# ADC-ADC_PSU.net
KiCad netlist of a schematic drawn in Altium Designer
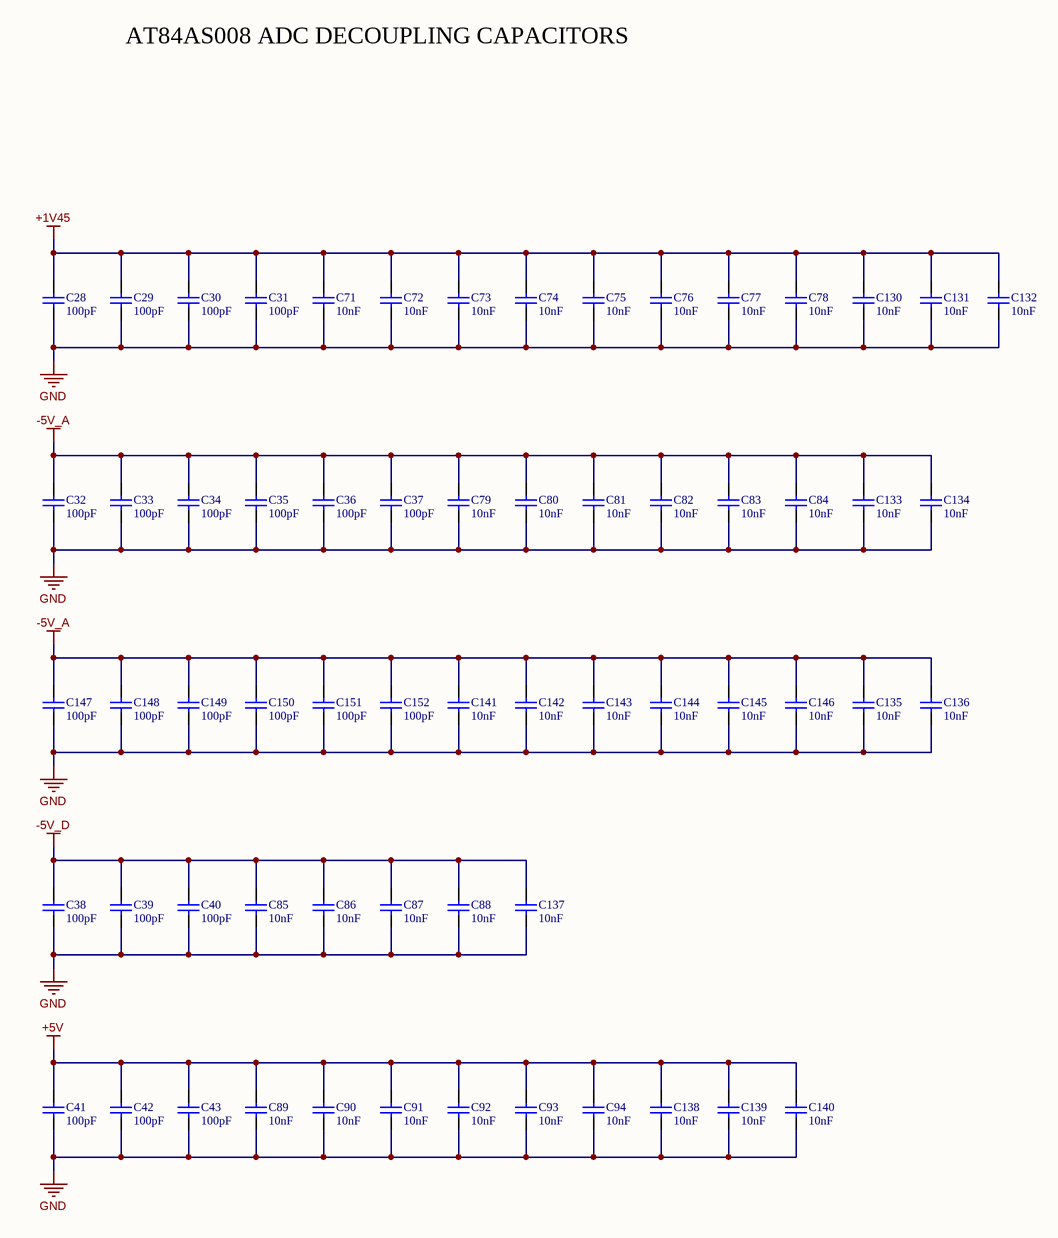
[diagram p0: ADC-ADC PSU.SchDoc]

(export (version "E")
  (design (tool "Eeschema 10.0.6"))
  (components
    (comp (ref "C28")
      (value "100pF")
      (footprint "CAPC1005X55N")
      (description "Capacitor 0402 SMD")
      (fields (field (name "CREATED_BY") "EDA-ASA") (field (name "CHECKED_BY") "*"))
      (libsource (lib "EDA-Passive") (part "cap0402"))
    )
    (comp (ref "C29")
      (value "100pF")
      (footprint "CAPC1005X55N")
      (description "Capacitor 0402 SMD")
      (fields (field (name "CREATED_BY") "EDA-ASA") (field (name "CHECKED_BY") "*"))
      (libsource (lib "EDA-Passive") (part "cap0402"))
    )
    (comp (ref "C30")
      (value "100pF")
      (footprint "CAPC1005X55N")
      (description "Capacitor 0402 SMD")
      (fields (field (name "CREATED_BY") "EDA-ASA") (field (name "CHECKED_BY") "*"))
      (libsource (lib "EDA-Passive") (part "cap0402"))
    )
    (comp (ref "C31")
      (value "100pF")
      (footprint "CAPC1005X55N")
      (description "Capacitor 0402 SMD")
      (fields (field (name "CREATED_BY") "EDA-ASA") (field (name "CHECKED_BY") "*"))
      (libsource (lib "EDA-Passive") (part "cap0402"))
    )
    (comp (ref "C32")
      (value "100pF")
      (footprint "CAPC1005X55N")
      (description "Capacitor 0402 SMD")
      (fields (field (name "CREATED_BY") "EDA-ASA") (field (name "CHECKED_BY") "*"))
      (libsource (lib "EDA-Passive") (part "cap0402"))
    )
    (comp (ref "C33")
      (value "100pF")
      (footprint "CAPC1005X55N")
      (description "Capacitor 0402 SMD")
      (fields (field (name "CREATED_BY") "EDA-ASA") (field (name "CHECKED_BY") "*"))
      (libsource (lib "EDA-Passive") (part "cap0402"))
    )
    (comp (ref "C34")
      (value "100pF")
      (footprint "CAPC1005X55N")
      (description "Capacitor 0402 SMD")
      (fields (field (name "CREATED_BY") "EDA-ASA") (field (name "CHECKED_BY") "*"))
      (libsource (lib "EDA-Passive") (part "cap0402"))
    )
    (comp (ref "C35")
      (value "100pF")
      (footprint "CAPC1005X55N")
      (description "Capacitor 0402 SMD")
      (fields (field (name "CREATED_BY") "EDA-ASA") (field (name "CHECKED_BY") "*"))
      (libsource (lib "EDA-Passive") (part "cap0402"))
    )
    (comp (ref "C36")
      (value "100pF")
      (footprint "CAPC1005X55N")
      (description "Capacitor 0402 SMD")
      (fields (field (name "CREATED_BY") "EDA-ASA") (field (name "CHECKED_BY") "*"))
      (libsource (lib "EDA-Passive") (part "cap0402"))
    )
    (comp (ref "C37")
      (value "100pF")
      (footprint "CAPC1005X55N")
      (description "Capacitor 0402 SMD")
      (fields (field (name "CREATED_BY") "EDA-ASA") (field (name "CHECKED_BY") "*"))
      (libsource (lib "EDA-Passive") (part "cap0402"))
    )
    (comp (ref "C38")
      (value "100pF")
      (footprint "CAPC1005X55N")
      (description "Capacitor 0402 SMD")
      (fields (field (name "CREATED_BY") "EDA-ASA") (field (name "CHECKED_BY") "*"))
      (libsource (lib "EDA-Passive") (part "cap0402"))
    )
    (comp (ref "C39")
      (value "100pF")
      (footprint "CAPC1005X55N")
      (description "Capacitor 0402 SMD")
      (fields (field (name "CREATED_BY") "EDA-ASA") (field (name "CHECKED_BY") "*"))
      (libsource (lib "EDA-Passive") (part "cap0402"))
    )
    (comp (ref "C40")
      (value "100pF")
      (footprint "CAPC1005X55N")
      (description "Capacitor 0402 SMD")
      (fields (field (name "CREATED_BY") "EDA-ASA") (field (name "CHECKED_BY") "*"))
      (libsource (lib "EDA-Passive") (part "cap0402"))
    )
    (comp (ref "C41")
      (value "100pF")
      (footprint "CAPC1005X55N")
      (description "Capacitor 0402 SMD")
      (fields (field (name "CREATED_BY") "EDA-ASA") (field (name "CHECKED_BY") "*"))
      (libsource (lib "EDA-Passive") (part "cap0402"))
    )
    (comp (ref "C42")
      (value "100pF")
      (footprint "CAPC1005X55N")
      (description "Capacitor 0402 SMD")
      (fields (field (name "CREATED_BY") "EDA-ASA") (field (name "CHECKED_BY") "*"))
      (libsource (lib "EDA-Passive") (part "cap0402"))
    )
    (comp (ref "C43")
      (value "100pF")
      (footprint "CAPC1005X55N")
      (description "Capacitor 0402 SMD")
      (fields (field (name "CREATED_BY") "EDA-ASA") (field (name "CHECKED_BY") "*"))
      (libsource (lib "EDA-Passive") (part "cap0402"))
    )
    (comp (ref "C71")
      (value "10nF")
      (footprint "CAPC1005X55N")
      (description "Capacitor 0402 SMD")
      (fields (field (name "CREATED_BY") "EDA-ASA") (field (name "CHECKED_BY") "*"))
      (libsource (lib "EDA-Passive") (part "cap0402"))
    )
    (comp (ref "C72")
      (value "10nF")
      (footprint "CAPC1005X55N")
      (description "Capacitor 0402 SMD")
      (fields (field (name "CREATED_BY") "EDA-ASA") (field (name "CHECKED_BY") "*"))
      (libsource (lib "EDA-Passive") (part "cap0402"))
    )
    (comp (ref "C73")
      (value "10nF")
      (footprint "CAPC1005X55N")
      (description "Capacitor 0402 SMD")
      (fields (field (name "CREATED_BY") "EDA-ASA") (field (name "CHECKED_BY") "*"))
      (libsource (lib "EDA-Passive") (part "cap0402"))
    )
    (comp (ref "C74")
      (value "10nF")
      (footprint "CAPC1005X55N")
      (description "Capacitor 0402 SMD")
      (fields (field (name "CREATED_BY") "EDA-ASA") (field (name "CHECKED_BY") "*"))
      (libsource (lib "EDA-Passive") (part "cap0402"))
    )
    (comp (ref "C75")
      (value "10nF")
      (footprint "CAPC1005X55N")
      (description "Capacitor 0402 SMD")
      (fields (field (name "CREATED_BY") "EDA-ASA") (field (name "CHECKED_BY") "*"))
      (libsource (lib "EDA-Passive") (part "cap0402"))
    )
    (comp (ref "C76")
      (value "10nF")
      (footprint "CAPC1005X55N")
      (description "Capacitor 0402 SMD")
      (fields (field (name "CREATED_BY") "EDA-ASA") (field (name "CHECKED_BY") "*"))
      (libsource (lib "EDA-Passive") (part "cap0402"))
    )
    (comp (ref "C77")
      (value "10nF")
      (footprint "CAPC1005X55N")
      (description "Capacitor 0402 SMD")
      (fields (field (name "CREATED_BY") "EDA-ASA") (field (name "CHECKED_BY") "*"))
      (libsource (lib "EDA-Passive") (part "cap0402"))
    )
    (comp (ref "C78")
      (value "10nF")
      (footprint "CAPC1005X55N")
      (description "Capacitor 0402 SMD")
      (fields (field (name "CREATED_BY") "EDA-ASA") (field (name "CHECKED_BY") "*"))
      (libsource (lib "EDA-Passive") (part "cap0402"))
    )
    (comp (ref "C79")
      (value "10nF")
      (footprint "CAPC1005X55N")
      (description "Capacitor 0402 SMD")
      (fields (field (name "CREATED_BY") "EDA-ASA") (field (name "CHECKED_BY") "*"))
      (libsource (lib "EDA-Passive") (part "cap0402"))
    )
    (comp (ref "C80")
      (value "10nF")
      (footprint "CAPC1005X55N")
      (description "Capacitor 0402 SMD")
      (fields (field (name "CREATED_BY") "EDA-ASA") (field (name "CHECKED_BY") "*"))
      (libsource (lib "EDA-Passive") (part "cap0402"))
    )
    (comp (ref "C81")
      (value "10nF")
      (footprint "CAPC1005X55N")
      (description "Capacitor 0402 SMD")
      (fields (field (name "CREATED_BY") "EDA-ASA") (field (name "CHECKED_BY") "*"))
      (libsource (lib "EDA-Passive") (part "cap0402"))
    )
    (comp (ref "C82")
      (value "10nF")
      (footprint "CAPC1005X55N")
      (description "Capacitor 0402 SMD")
      (fields (field (name "CREATED_BY") "EDA-ASA") (field (name "CHECKED_BY") "*"))
      (libsource (lib "EDA-Passive") (part "cap0402"))
    )
    (comp (ref "C83")
      (value "10nF")
      (footprint "CAPC1005X55N")
      (description "Capacitor 0402 SMD")
      (fields (field (name "CREATED_BY") "EDA-ASA") (field (name "CHECKED_BY") "*"))
      (libsource (lib "EDA-Passive") (part "cap0402"))
    )
    (comp (ref "C84")
      (value "10nF")
      (footprint "CAPC1005X55N")
      (description "Capacitor 0402 SMD")
      (fields (field (name "CREATED_BY") "EDA-ASA") (field (name "CHECKED_BY") "*"))
      (libsource (lib "EDA-Passive") (part "cap0402"))
    )
    (comp (ref "C85")
      (value "10nF")
      (footprint "CAPC1005X55N")
      (description "Capacitor 0402 SMD")
      (fields (field (name "CREATED_BY") "EDA-ASA") (field (name "CHECKED_BY") "*"))
      (libsource (lib "EDA-Passive") (part "cap0402"))
    )
    (comp (ref "C86")
      (value "10nF")
      (footprint "CAPC1005X55N")
      (description "Capacitor 0402 SMD")
      (fields (field (name "CREATED_BY") "EDA-ASA") (field (name "CHECKED_BY") "*"))
      (libsource (lib "EDA-Passive") (part "cap0402"))
    )
    (comp (ref "C87")
      (value "10nF")
      (footprint "CAPC1005X55N")
      (description "Capacitor 0402 SMD")
      (fields (field (name "CREATED_BY") "EDA-ASA") (field (name "CHECKED_BY") "*"))
      (libsource (lib "EDA-Passive") (part "cap0402"))
    )
    (comp (ref "C88")
      (value "10nF")
      (footprint "CAPC1005X55N")
      (description "Capacitor 0402 SMD")
      (fields (field (name "CREATED_BY") "EDA-ASA") (field (name "CHECKED_BY") "*"))
      (libsource (lib "EDA-Passive") (part "cap0402"))
    )
    (comp (ref "C89")
      (value "10nF")
      (footprint "CAPC1005X55N")
      (description "Capacitor 0402 SMD")
      (fields (field (name "CREATED_BY") "EDA-ASA") (field (name "CHECKED_BY") "*"))
      (libsource (lib "EDA-Passive") (part "cap0402"))
    )
    (comp (ref "C90")
      (value "10nF")
      (footprint "CAPC1005X55N")
      (description "Capacitor 0402 SMD")
      (fields (field (name "CREATED_BY") "EDA-ASA") (field (name "CHECKED_BY") "*"))
      (libsource (lib "EDA-Passive") (part "cap0402"))
    )
    (comp (ref "C91")
      (value "10nF")
      (footprint "CAPC1005X55N")
      (description "Capacitor 0402 SMD")
      (fields (field (name "CREATED_BY") "EDA-ASA") (field (name "CHECKED_BY") "*"))
      (libsource (lib "EDA-Passive") (part "cap0402"))
    )
    (comp (ref "C92")
      (value "10nF")
      (footprint "CAPC1005X55N")
      (description "Capacitor 0402 SMD")
      (fields (field (name "CREATED_BY") "EDA-ASA") (field (name "CHECKED_BY") "*"))
      (libsource (lib "EDA-Passive") (part "cap0402"))
    )
    (comp (ref "C93")
      (value "10nF")
      (footprint "CAPC1005X55N")
      (description "Capacitor 0402 SMD")
      (fields (field (name "CREATED_BY") "EDA-ASA") (field (name "CHECKED_BY") "*"))
      (libsource (lib "EDA-Passive") (part "cap0402"))
    )
    (comp (ref "C94")
      (value "10nF")
      (footprint "CAPC1005X55N")
      (description "Capacitor 0402 SMD")
      (fields (field (name "CREATED_BY") "EDA-ASA") (field (name "CHECKED_BY") "*"))
      (libsource (lib "EDA-Passive") (part "cap0402"))
    )
    (comp (ref "C130")
      (value "10nF")
      (footprint "CAPC1005X55N")
      (description "Capacitor 0402 SMD")
      (fields (field (name "CREATED_BY") "EDA-ASA") (field (name "CHECKED_BY") "*"))
      (libsource (lib "EDA-Passive") (part "cap0402"))
    )
    (comp (ref "C131")
      (value "10nF")
      (footprint "CAPC1005X55N")
      (description "Capacitor 0402 SMD")
      (fields (field (name "CREATED_BY") "EDA-ASA") (field (name "CHECKED_BY") "*"))
      (libsource (lib "EDA-Passive") (part "cap0402"))
    )
    (comp (ref "C132")
      (value "10nF")
      (footprint "CAPC1005X55N")
      (description "Capacitor 0402 SMD")
      (fields (field (name "CREATED_BY") "EDA-ASA") (field (name "CHECKED_BY") "*"))
      (libsource (lib "EDA-Passive") (part "cap0402"))
    )
    (comp (ref "C133")
      (value "10nF")
      (footprint "CAPC1005X55N")
      (description "Capacitor 0402 SMD")
      (fields (field (name "CREATED_BY") "EDA-ASA") (field (name "CHECKED_BY") "*"))
      (libsource (lib "EDA-Passive") (part "cap0402"))
    )
    (comp (ref "C134")
      (value "10nF")
      (footprint "CAPC1005X55N")
      (description "Capacitor 0402 SMD")
      (fields (field (name "CREATED_BY") "EDA-ASA") (field (name "CHECKED_BY") "*"))
      (libsource (lib "EDA-Passive") (part "cap0402"))
    )
    (comp (ref "C135")
      (value "10nF")
      (footprint "CAPC1005X55N")
      (description "Capacitor 0402 SMD")
      (fields (field (name "CREATED_BY") "EDA-ASA") (field (name "CHECKED_BY") "*"))
      (libsource (lib "EDA-Passive") (part "cap0402"))
    )
    (comp (ref "C136")
      (value "10nF")
      (footprint "CAPC1005X55N")
      (description "Capacitor 0402 SMD")
      (fields (field (name "CREATED_BY") "EDA-ASA") (field (name "CHECKED_BY") "*"))
      (libsource (lib "EDA-Passive") (part "cap0402"))
    )
    (comp (ref "C137")
      (value "10nF")
      (footprint "CAPC1005X55N")
      (description "Capacitor 0402 SMD")
      (fields (field (name "CREATED_BY") "EDA-ASA") (field (name "CHECKED_BY") "*"))
      (libsource (lib "EDA-Passive") (part "cap0402"))
    )
    (comp (ref "C138")
      (value "10nF")
      (footprint "CAPC1005X55N")
      (description "Capacitor 0402 SMD")
      (fields (field (name "CREATED_BY") "EDA-ASA") (field (name "CHECKED_BY") "*"))
      (libsource (lib "EDA-Passive") (part "cap0402"))
    )
    (comp (ref "C139")
      (value "10nF")
      (footprint "CAPC1005X55N")
      (description "Capacitor 0402 SMD")
      (fields (field (name "CREATED_BY") "EDA-ASA") (field (name "CHECKED_BY") "*"))
      (libsource (lib "EDA-Passive") (part "cap0402"))
    )
    (comp (ref "C140")
      (value "10nF")
      (footprint "CAPC1005X55N")
      (description "Capacitor 0402 SMD")
      (fields (field (name "CREATED_BY") "EDA-ASA") (field (name "CHECKED_BY") "*"))
      (libsource (lib "EDA-Passive") (part "cap0402"))
    )
    (comp (ref "C141")
      (value "10nF")
      (footprint "CAPC1005X55N")
      (description "Capacitor 0402 SMD")
      (fields (field (name "CREATED_BY") "EDA-ASA") (field (name "CHECKED_BY") "*"))
      (libsource (lib "EDA-Passive") (part "cap0402"))
    )
    (comp (ref "C142")
      (value "10nF")
      (footprint "CAPC1005X55N")
      (description "Capacitor 0402 SMD")
      (fields (field (name "CREATED_BY") "EDA-ASA") (field (name "CHECKED_BY") "*"))
      (libsource (lib "EDA-Passive") (part "cap0402"))
    )
    (comp (ref "C143")
      (value "10nF")
      (footprint "CAPC1005X55N")
      (description "Capacitor 0402 SMD")
      (fields (field (name "CREATED_BY") "EDA-ASA") (field (name "CHECKED_BY") "*"))
      (libsource (lib "EDA-Passive") (part "cap0402"))
    )
    (comp (ref "C144")
      (value "10nF")
      (footprint "CAPC1005X55N")
      (description "Capacitor 0402 SMD")
      (fields (field (name "CREATED_BY") "EDA-ASA") (field (name "CHECKED_BY") "*"))
      (libsource (lib "EDA-Passive") (part "cap0402"))
    )
    (comp (ref "C145")
      (value "10nF")
      (footprint "CAPC1005X55N")
      (description "Capacitor 0402 SMD")
      (fields (field (name "CREATED_BY") "EDA-ASA") (field (name "CHECKED_BY") "*"))
      (libsource (lib "EDA-Passive") (part "cap0402"))
    )
    (comp (ref "C146")
      (value "10nF")
      (footprint "CAPC1005X55N")
      (description "Capacitor 0402 SMD")
      (fields (field (name "CREATED_BY") "EDA-ASA") (field (name "CHECKED_BY") "*"))
      (libsource (lib "EDA-Passive") (part "cap0402"))
    )
    (comp (ref "C147")
      (value "100pF")
      (footprint "CAPC1005X55N")
      (description "Capacitor 0402 SMD")
      (fields (field (name "CREATED_BY") "EDA-ASA") (field (name "CHECKED_BY") "*"))
      (libsource (lib "EDA-Passive") (part "cap0402"))
    )
    (comp (ref "C148")
      (value "100pF")
      (footprint "CAPC1005X55N")
      (description "Capacitor 0402 SMD")
      (fields (field (name "CREATED_BY") "EDA-ASA") (field (name "CHECKED_BY") "*"))
      (libsource (lib "EDA-Passive") (part "cap0402"))
    )
    (comp (ref "C149")
      (value "100pF")
      (footprint "CAPC1005X55N")
      (description "Capacitor 0402 SMD")
      (fields (field (name "CREATED_BY") "EDA-ASA") (field (name "CHECKED_BY") "*"))
      (libsource (lib "EDA-Passive") (part "cap0402"))
    )
    (comp (ref "C150")
      (value "100pF")
      (footprint "CAPC1005X55N")
      (description "Capacitor 0402 SMD")
      (fields (field (name "CREATED_BY") "EDA-ASA") (field (name "CHECKED_BY") "*"))
      (libsource (lib "EDA-Passive") (part "cap0402"))
    )
    (comp (ref "C151")
      (value "100pF")
      (footprint "CAPC1005X55N")
      (description "Capacitor 0402 SMD")
      (fields (field (name "CREATED_BY") "EDA-ASA") (field (name "CHECKED_BY") "*"))
      (libsource (lib "EDA-Passive") (part "cap0402"))
    )
    (comp (ref "C152")
      (value "100pF")
      (footprint "CAPC1005X55N")
      (description "Capacitor 0402 SMD")
      (fields (field (name "CREATED_BY") "EDA-ASA") (field (name "CHECKED_BY") "*"))
      (libsource (lib "EDA-Passive") (part "cap0402"))
    )
  )
  (nets
    (net (code "1") (name "+1V45") (class "Default")
      (node (ref "C130") (pin "1") (pinfunction "1_1") (pintype "passive"))
      (node (ref "C131") (pin "1") (pinfunction "1_1") (pintype "passive"))
      (node (ref "C132") (pin "1") (pinfunction "1_1") (pintype "passive"))
      (node (ref "C28") (pin "1") (pinfunction "1_1") (pintype "passive"))
      (node (ref "C29") (pin "1") (pinfunction "1_1") (pintype "passive"))
      (node (ref "C30") (pin "1") (pinfunction "1_1") (pintype "passive"))
      (node (ref "C31") (pin "1") (pinfunction "1_1") (pintype "passive"))
      (node (ref "C71") (pin "1") (pinfunction "1_1") (pintype "passive"))
      (node (ref "C72") (pin "1") (pinfunction "1_1") (pintype "passive"))
      (node (ref "C73") (pin "1") (pinfunction "1_1") (pintype "passive"))
      (node (ref "C74") (pin "1") (pinfunction "1_1") (pintype "passive"))
      (node (ref "C75") (pin "1") (pinfunction "1_1") (pintype "passive"))
      (node (ref "C76") (pin "1") (pinfunction "1_1") (pintype "passive"))
      (node (ref "C77") (pin "1") (pinfunction "1_1") (pintype "passive"))
      (node (ref "C78") (pin "1") (pinfunction "1_1") (pintype "passive"))
    )
    (net (code "2") (name "+5V") (class "Default")
      (node (ref "C138") (pin "1") (pinfunction "1_1") (pintype "passive"))
      (node (ref "C139") (pin "1") (pinfunction "1_1") (pintype "passive"))
      (node (ref "C140") (pin "1") (pinfunction "1_1") (pintype "passive"))
      (node (ref "C41") (pin "1") (pinfunction "1_1") (pintype "passive"))
      (node (ref "C42") (pin "1") (pinfunction "1_1") (pintype "passive"))
      (node (ref "C43") (pin "1") (pinfunction "1_1") (pintype "passive"))
      (node (ref "C89") (pin "1") (pinfunction "1_1") (pintype "passive"))
      (node (ref "C90") (pin "1") (pinfunction "1_1") (pintype "passive"))
      (node (ref "C91") (pin "1") (pinfunction "1_1") (pintype "passive"))
      (node (ref "C92") (pin "1") (pinfunction "1_1") (pintype "passive"))
      (node (ref "C93") (pin "1") (pinfunction "1_1") (pintype "passive"))
      (node (ref "C94") (pin "1") (pinfunction "1_1") (pintype "passive"))
    )
    (net (code "3") (name "-5V_A") (class "Default")
      (node (ref "C133") (pin "1") (pinfunction "1_1") (pintype "passive"))
      (node (ref "C134") (pin "1") (pinfunction "1_1") (pintype "passive"))
      (node (ref "C135") (pin "1") (pinfunction "1_1") (pintype "passive"))
      (node (ref "C136") (pin "1") (pinfunction "1_1") (pintype "passive"))
      (node (ref "C141") (pin "1") (pinfunction "1_1") (pintype "passive"))
      (node (ref "C142") (pin "1") (pinfunction "1_1") (pintype "passive"))
      (node (ref "C143") (pin "1") (pinfunction "1_1") (pintype "passive"))
      (node (ref "C144") (pin "1") (pinfunction "1_1") (pintype "passive"))
      (node (ref "C145") (pin "1") (pinfunction "1_1") (pintype "passive"))
      (node (ref "C146") (pin "1") (pinfunction "1_1") (pintype "passive"))
      (node (ref "C147") (pin "1") (pinfunction "1_1") (pintype "passive"))
      (node (ref "C148") (pin "1") (pinfunction "1_1") (pintype "passive"))
      (node (ref "C149") (pin "1") (pinfunction "1_1") (pintype "passive"))
      (node (ref "C150") (pin "1") (pinfunction "1_1") (pintype "passive"))
      (node (ref "C151") (pin "1") (pinfunction "1_1") (pintype "passive"))
      (node (ref "C152") (pin "1") (pinfunction "1_1") (pintype "passive"))
      (node (ref "C32") (pin "1") (pinfunction "1_1") (pintype "passive"))
      (node (ref "C33") (pin "1") (pinfunction "1_1") (pintype "passive"))
      (node (ref "C34") (pin "1") (pinfunction "1_1") (pintype "passive"))
      (node (ref "C35") (pin "1") (pinfunction "1_1") (pintype "passive"))
      (node (ref "C36") (pin "1") (pinfunction "1_1") (pintype "passive"))
      (node (ref "C37") (pin "1") (pinfunction "1_1") (pintype "passive"))
      (node (ref "C79") (pin "1") (pinfunction "1_1") (pintype "passive"))
      (node (ref "C80") (pin "1") (pinfunction "1_1") (pintype "passive"))
      (node (ref "C81") (pin "1") (pinfunction "1_1") (pintype "passive"))
      (node (ref "C82") (pin "1") (pinfunction "1_1") (pintype "passive"))
      (node (ref "C83") (pin "1") (pinfunction "1_1") (pintype "passive"))
      (node (ref "C84") (pin "1") (pinfunction "1_1") (pintype "passive"))
    )
    (net (code "4") (name "-5V_D") (class "Default")
      (node (ref "C137") (pin "1") (pinfunction "1_1") (pintype "passive"))
      (node (ref "C38") (pin "1") (pinfunction "1_1") (pintype "passive"))
      (node (ref "C39") (pin "1") (pinfunction "1_1") (pintype "passive"))
      (node (ref "C40") (pin "1") (pinfunction "1_1") (pintype "passive"))
      (node (ref "C85") (pin "1") (pinfunction "1_1") (pintype "passive"))
      (node (ref "C86") (pin "1") (pinfunction "1_1") (pintype "passive"))
      (node (ref "C87") (pin "1") (pinfunction "1_1") (pintype "passive"))
      (node (ref "C88") (pin "1") (pinfunction "1_1") (pintype "passive"))
    )
    (net (code "5") (name "GND") (class "Default")
      (node (ref "C130") (pin "2") (pinfunction "2_2") (pintype "passive"))
      (node (ref "C131") (pin "2") (pinfunction "2_2") (pintype "passive"))
      (node (ref "C132") (pin "2") (pinfunction "2_2") (pintype "passive"))
      (node (ref "C133") (pin "2") (pinfunction "2_2") (pintype "passive"))
      (node (ref "C134") (pin "2") (pinfunction "2_2") (pintype "passive"))
      (node (ref "C135") (pin "2") (pinfunction "2_2") (pintype "passive"))
      (node (ref "C136") (pin "2") (pinfunction "2_2") (pintype "passive"))
      (node (ref "C137") (pin "2") (pinfunction "2_2") (pintype "passive"))
      (node (ref "C138") (pin "2") (pinfunction "2_2") (pintype "passive"))
      (node (ref "C139") (pin "2") (pinfunction "2_2") (pintype "passive"))
      (node (ref "C140") (pin "2") (pinfunction "2_2") (pintype "passive"))
      (node (ref "C141") (pin "2") (pinfunction "2_2") (pintype "passive"))
      (node (ref "C142") (pin "2") (pinfunction "2_2") (pintype "passive"))
      (node (ref "C143") (pin "2") (pinfunction "2_2") (pintype "passive"))
      (node (ref "C144") (pin "2") (pinfunction "2_2") (pintype "passive"))
      (node (ref "C145") (pin "2") (pinfunction "2_2") (pintype "passive"))
      (node (ref "C146") (pin "2") (pinfunction "2_2") (pintype "passive"))
      (node (ref "C147") (pin "2") (pinfunction "2_2") (pintype "passive"))
      (node (ref "C148") (pin "2") (pinfunction "2_2") (pintype "passive"))
      (node (ref "C149") (pin "2") (pinfunction "2_2") (pintype "passive"))
      (node (ref "C150") (pin "2") (pinfunction "2_2") (pintype "passive"))
      (node (ref "C151") (pin "2") (pinfunction "2_2") (pintype "passive"))
      (node (ref "C152") (pin "2") (pinfunction "2_2") (pintype "passive"))
      (node (ref "C28") (pin "2") (pinfunction "2_2") (pintype "passive"))
      (node (ref "C29") (pin "2") (pinfunction "2_2") (pintype "passive"))
      (node (ref "C30") (pin "2") (pinfunction "2_2") (pintype "passive"))
      (node (ref "C31") (pin "2") (pinfunction "2_2") (pintype "passive"))
      (node (ref "C32") (pin "2") (pinfunction "2_2") (pintype "passive"))
      (node (ref "C33") (pin "2") (pinfunction "2_2") (pintype "passive"))
      (node (ref "C34") (pin "2") (pinfunction "2_2") (pintype "passive"))
      (node (ref "C35") (pin "2") (pinfunction "2_2") (pintype "passive"))
      (node (ref "C36") (pin "2") (pinfunction "2_2") (pintype "passive"))
      (node (ref "C37") (pin "2") (pinfunction "2_2") (pintype "passive"))
      (node (ref "C38") (pin "2") (pinfunction "2_2") (pintype "passive"))
      (node (ref "C39") (pin "2") (pinfunction "2_2") (pintype "passive"))
      (node (ref "C40") (pin "2") (pinfunction "2_2") (pintype "passive"))
      (node (ref "C41") (pin "2") (pinfunction "2_2") (pintype "passive"))
      (node (ref "C42") (pin "2") (pinfunction "2_2") (pintype "passive"))
      (node (ref "C43") (pin "2") (pinfunction "2_2") (pintype "passive"))
      (node (ref "C71") (pin "2") (pinfunction "2_2") (pintype "passive"))
      (node (ref "C72") (pin "2") (pinfunction "2_2") (pintype "passive"))
      (node (ref "C73") (pin "2") (pinfunction "2_2") (pintype "passive"))
      (node (ref "C74") (pin "2") (pinfunction "2_2") (pintype "passive"))
      (node (ref "C75") (pin "2") (pinfunction "2_2") (pintype "passive"))
      (node (ref "C76") (pin "2") (pinfunction "2_2") (pintype "passive"))
      (node (ref "C77") (pin "2") (pinfunction "2_2") (pintype "passive"))
      (node (ref "C78") (pin "2") (pinfunction "2_2") (pintype "passive"))
      (node (ref "C79") (pin "2") (pinfunction "2_2") (pintype "passive"))
      (node (ref "C80") (pin "2") (pinfunction "2_2") (pintype "passive"))
      (node (ref "C81") (pin "2") (pinfunction "2_2") (pintype "passive"))
      (node (ref "C82") (pin "2") (pinfunction "2_2") (pintype "passive"))
      (node (ref "C83") (pin "2") (pinfunction "2_2") (pintype "passive"))
      (node (ref "C84") (pin "2") (pinfunction "2_2") (pintype "passive"))
      (node (ref "C85") (pin "2") (pinfunction "2_2") (pintype "passive"))
      (node (ref "C86") (pin "2") (pinfunction "2_2") (pintype "passive"))
      (node (ref "C87") (pin "2") (pinfunction "2_2") (pintype "passive"))
      (node (ref "C88") (pin "2") (pinfunction "2_2") (pintype "passive"))
      (node (ref "C89") (pin "2") (pinfunction "2_2") (pintype "passive"))
      (node (ref "C90") (pin "2") (pinfunction "2_2") (pintype "passive"))
      (node (ref "C91") (pin "2") (pinfunction "2_2") (pintype "passive"))
      (node (ref "C92") (pin "2") (pinfunction "2_2") (pintype "passive"))
      (node (ref "C93") (pin "2") (pinfunction "2_2") (pintype "passive"))
      (node (ref "C94") (pin "2") (pinfunction "2_2") (pintype "passive"))
    )
  )
)
